# chariot_power_a2.net
KiCad netlist of a schematic drawn in EAGLE
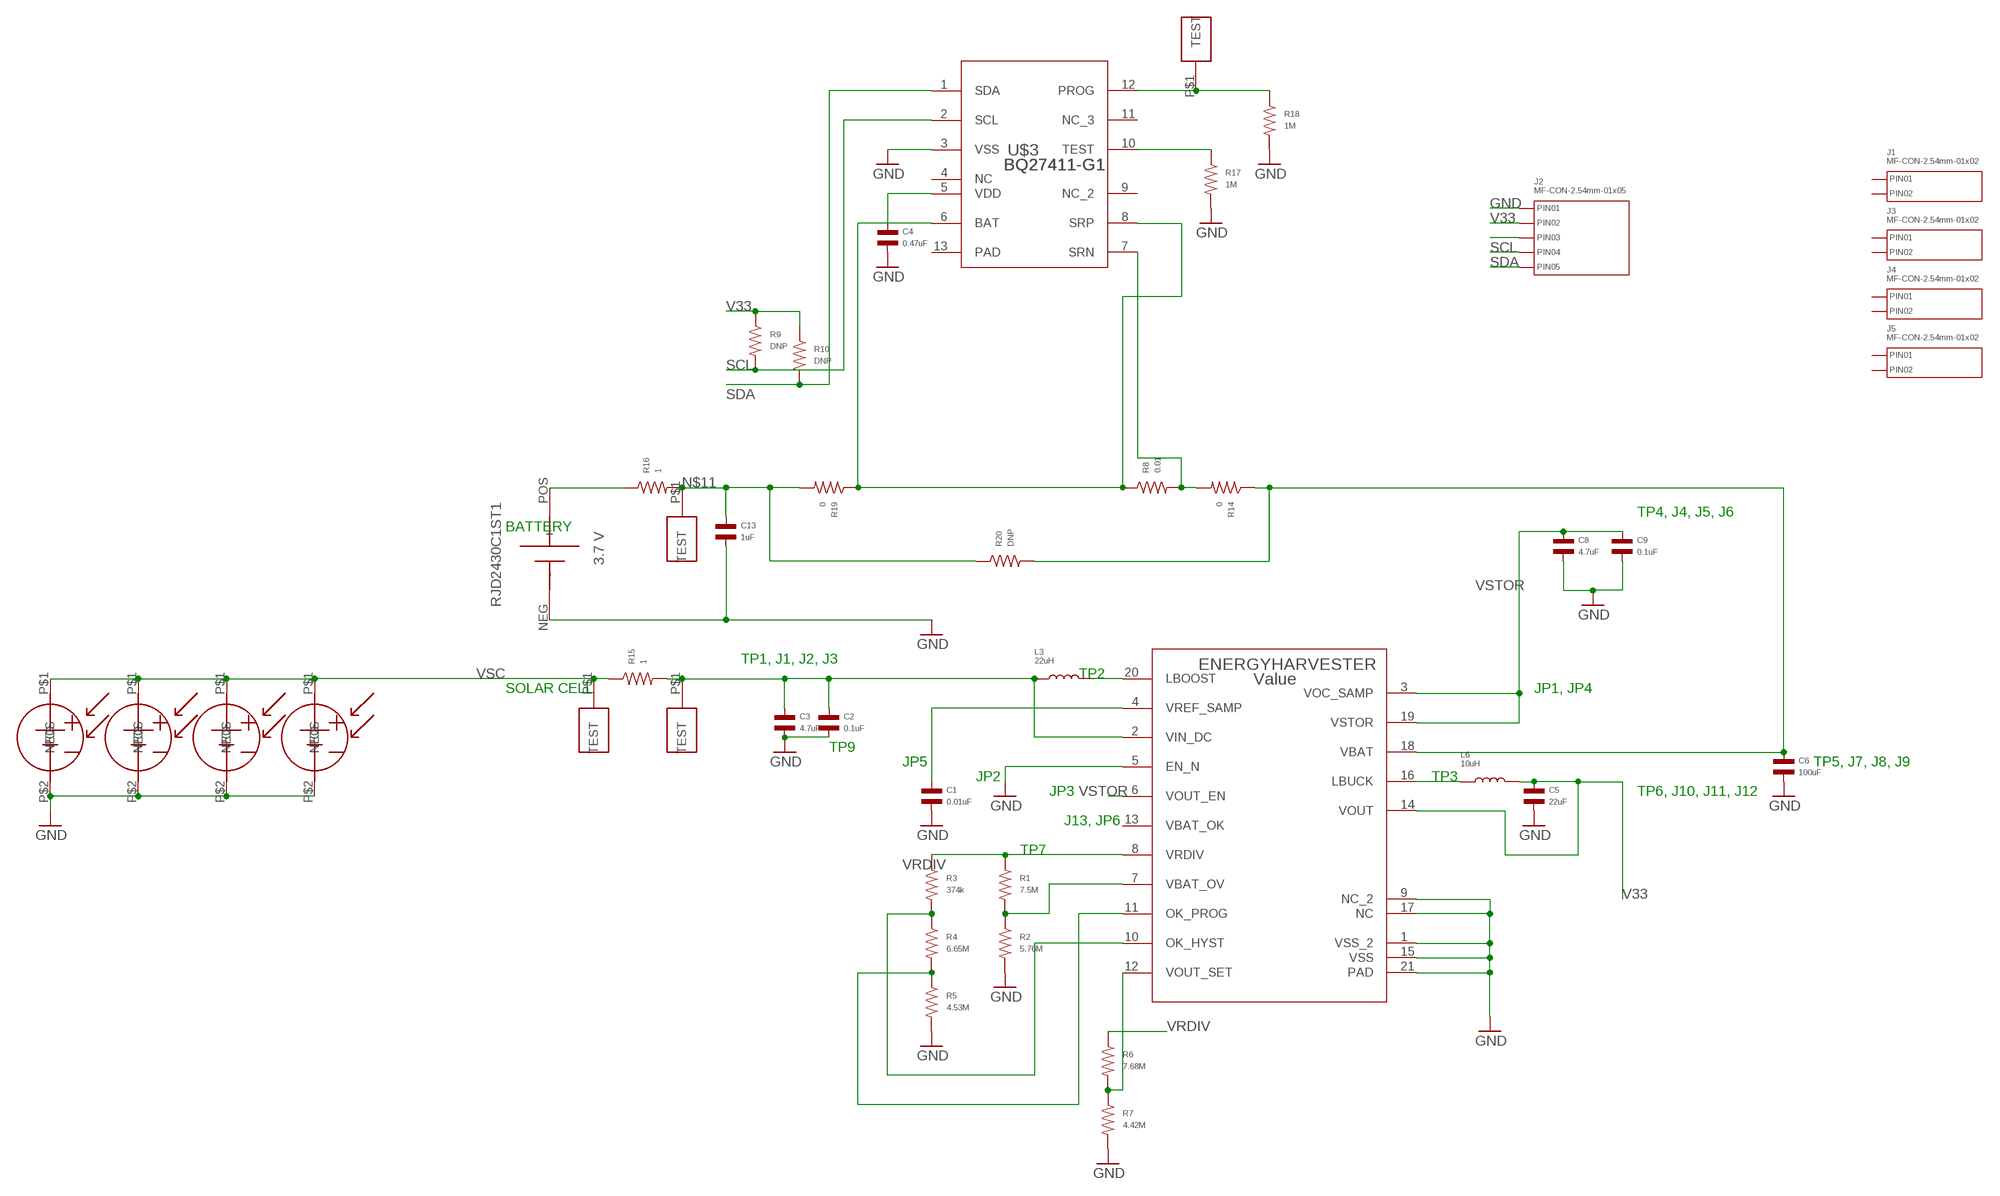
[diagram p0: schematic, sheet 1]

(export (version "E")
  (design (tool "Eeschema 10.0.6"))
  (components
    (comp (ref "C1")
      (value "0.01uF")
      (footprint "eagle-import:C0603")
      (libsource (lib "eagle-import") (part "CAPACITOR_NP_0603"))
    )
    (comp (ref "C2")
      (value "0.1uF")
      (footprint "eagle-import:C0603")
      (libsource (lib "eagle-import") (part "CAPACITOR_NP_0603"))
    )
    (comp (ref "C3")
      (value "4.7uF")
      (footprint "eagle-import:C0603")
      (libsource (lib "eagle-import") (part "CAPACITOR_NP_0603"))
    )
    (comp (ref "C4")
      (value "0.47uF")
      (footprint "eagle-import:C0603")
      (libsource (lib "eagle-import") (part "CAPACITOR_NP_0603"))
    )
    (comp (ref "C5")
      (value "22uF")
      (footprint "eagle-import:C0603")
      (libsource (lib "eagle-import") (part "CAPACITOR_NP_0603"))
    )
    (comp (ref "C6")
      (value "100uF")
      (footprint "eagle-import:C0805")
      (libsource (lib "eagle-import") (part "CAPACITOR_NP_0805"))
    )
    (comp (ref "C8")
      (value "4.7uF")
      (footprint "eagle-import:C0603")
      (libsource (lib "eagle-import") (part "CAPACITOR_NP_0603"))
    )
    (comp (ref "C9")
      (value "0.1uF")
      (footprint "eagle-import:C0603")
      (libsource (lib "eagle-import") (part "CAPACITOR_NP_0603"))
    )
    (comp (ref "C13")
      (value "1uF")
      (footprint "eagle-import:C0603")
      (libsource (lib "eagle-import") (part "CAPACITOR_NP_0603"))
    )
    (comp (ref "ENERGYHARVESTER")
      (value "Value")
      (footprint "eagle-import:RGR0020A")
      (fields
        (field (name "ALTERNATEPARTNUMBER") "BQ25570RGRT")
        (field (name "MANUFACTURER") "Texas Instruments")
        (field (name "PARTNUMBER") "BQ25570RGRR")
      )
      (libsource (lib "eagle-import") (part "BQ25570RGRR"))
    )
    (comp (ref "J1")
      (value "MF-CON-2.54mm-01x02")
      (footprint "eagle-import:PTH_2.54MM_01X02")
      (fields (field (name "HOUSEPART") "YES"))
      (libsource (lib "eagle-import") (part "CON_01X02_PTH_2.54MM"))
    )
    (comp (ref "J2")
      (value "MF-CON-2.54mm-01x05")
      (footprint "eagle-import:PTH_2.54MM_01X05")
      (fields (field (name "HOUSEPART") "YES"))
      (libsource (lib "eagle-import") (part "CON_01X05_PTH_2.54MM"))
    )
    (comp (ref "J3")
      (value "MF-CON-2.54mm-01x02")
      (footprint "eagle-import:PTH_2.54MM_01X02")
      (fields (field (name "HOUSEPART") "YES"))
      (libsource (lib "eagle-import") (part "CON_01X02_PTH_2.54MM"))
    )
    (comp (ref "J4")
      (value "MF-CON-2.54mm-01x02")
      (footprint "eagle-import:PTH_2.54MM_01X02")
      (fields (field (name "HOUSEPART") "YES"))
      (libsource (lib "eagle-import") (part "CON_01X02_PTH_2.54MM"))
    )
    (comp (ref "J5")
      (value "MF-CON-2.54mm-01x02")
      (footprint "eagle-import:PTH_2.54MM_01X02")
      (fields (field (name "HOUSEPART") "YES"))
      (libsource (lib "eagle-import") (part "CON_01X02_PTH_2.54MM"))
    )
    (comp (ref "L3")
      (value "22uH")
      (footprint "eagle-import:L0603")
      (libsource (lib "eagle-import") (part "INDUCTOR_0603"))
    )
    (comp (ref "L6")
      (value "10uH")
      (footprint "eagle-import:L0603")
      (libsource (lib "eagle-import") (part "INDUCTOR_0603"))
    )
    (comp (ref "R1")
      (value "7.5M")
      (footprint "eagle-import:R0603")
      (libsource (lib "eagle-import") (part "RESISTOR_0603"))
    )
    (comp (ref "R2")
      (value "5.76M")
      (footprint "eagle-import:R0603")
      (libsource (lib "eagle-import") (part "RESISTOR_0603"))
    )
    (comp (ref "R3")
      (value "374k")
      (footprint "eagle-import:R0603")
      (libsource (lib "eagle-import") (part "RESISTOR_0603"))
    )
    (comp (ref "R4")
      (value "6.65M")
      (footprint "eagle-import:R0603")
      (libsource (lib "eagle-import") (part "RESISTOR_0603"))
    )
    (comp (ref "R5")
      (value "4.53M")
      (footprint "eagle-import:R0603")
      (libsource (lib "eagle-import") (part "RESISTOR_0603"))
    )
    (comp (ref "R6")
      (value "7.68M")
      (footprint "eagle-import:R0603")
      (libsource (lib "eagle-import") (part "RESISTOR_0603"))
    )
    (comp (ref "R7")
      (value "4.42M")
      (footprint "eagle-import:R0603")
      (libsource (lib "eagle-import") (part "RESISTOR_0603"))
    )
    (comp (ref "R8")
      (value "0.01")
      (footprint "eagle-import:R0603")
      (libsource (lib "eagle-import") (part "RESISTOR_0603"))
    )
    (comp (ref "R9")
      (value "DNP")
      (footprint "eagle-import:R0603")
      (libsource (lib "eagle-import") (part "RESISTOR_0603"))
    )
    (comp (ref "R10")
      (value "DNP")
      (footprint "eagle-import:R0603")
      (libsource (lib "eagle-import") (part "RESISTOR_0603"))
    )
    (comp (ref "R14")
      (value "0")
      (footprint "eagle-import:R0603")
      (libsource (lib "eagle-import") (part "RESISTOR_0603"))
    )
    (comp (ref "R15")
      (value "1")
      (footprint "eagle-import:R0603")
      (libsource (lib "eagle-import") (part "RESISTOR_0603"))
    )
    (comp (ref "R16")
      (value "1")
      (footprint "eagle-import:R0603")
      (libsource (lib "eagle-import") (part "RESISTOR_0603"))
    )
    (comp (ref "R17")
      (value "1M")
      (footprint "eagle-import:R0603")
      (libsource (lib "eagle-import") (part "RESISTOR_0603"))
    )
    (comp (ref "R18")
      (value "1M")
      (footprint "eagle-import:R0603")
      (libsource (lib "eagle-import") (part "RESISTOR_0603"))
    )
    (comp (ref "R19")
      (value "0")
      (footprint "eagle-import:R0603")
      (libsource (lib "eagle-import") (part "RESISTOR_0603"))
    )
    (comp (ref "R20")
      (value "DNP")
      (footprint "eagle-import:R0603")
      (libsource (lib "eagle-import") (part "RESISTOR_0603"))
    )
    (comp (ref "TP4")
      (value "TESTPOINT_LOOP")
      (footprint "eagle-import:TESTPOINT_LOOP")
      (libsource (lib "eagle-import") (part "TESTPOINT_LOOP"))
    )
    (comp (ref "TP6")
      (value "TESTPOINT_LOOP")
      (footprint "eagle-import:TESTPOINT_LOOP")
      (libsource (lib "eagle-import") (part "TESTPOINT_LOOP"))
    )
    (comp (ref "TP7")
      (value "TESTPOINT_LOOP")
      (footprint "eagle-import:TESTPOINT_LOOP")
      (libsource (lib "eagle-import") (part "TESTPOINT_LOOP"))
    )
    (comp (ref "TP8")
      (value "TESTPOINT_LOOP")
      (footprint "eagle-import:TESTPOINT_LOOP")
      (libsource (lib "eagle-import") (part "TESTPOINT_LOOP"))
    )
    (comp (ref "U$2")
      (value "RJD2430C1ST1.")
      (footprint "eagle-import:RJD2430C1ST1")
      (libsource (lib "eagle-import") (part "RJD2430C1ST1."))
    )
    (comp (ref "U$3")
      (value "BQ27411-G1")
      (footprint "eagle-import:DRZ0012A")
      (libsource (lib "eagle-import") (part "BQ27411-G1"))
    )
    (comp (ref "U$4")
      (value "SOLARCELL722")
      (footprint "eagle-import:SOLARCELL722")
      (libsource (lib "eagle-import") (part "SOLARCELL722"))
    )
    (comp (ref "U$5")
      (value "SOLARCELL722")
      (footprint "eagle-import:SOLARCELL722")
      (libsource (lib "eagle-import") (part "SOLARCELL722"))
    )
    (comp (ref "U$6")
      (value "SOLARCELL722")
      (footprint "eagle-import:SOLARCELL722")
      (libsource (lib "eagle-import") (part "SOLARCELL722"))
    )
    (comp (ref "U$7")
      (value "SOLARCELL722")
      (footprint "eagle-import:SOLARCELL722")
      (libsource (lib "eagle-import") (part "SOLARCELL722"))
    )
  )
  (nets
    (net (code "1") (name "/N$11") (class "Default")
      (node (ref "C13") (pin "P$1") (pinfunction "P$1_P$1") (pintype "passive"))
      (node (ref "R16") (pin "P$2") (pinfunction "P$2_P$2") (pintype "passive"))
      (node (ref "R19") (pin "P$2") (pinfunction "P$2_P$2") (pintype "passive"))
      (node (ref "R20") (pin "P$1") (pinfunction "P$1_P$1") (pintype "passive"))
      (node (ref "TP7") (pin "P$1") (pinfunction "TEST_P$1") (pintype "bidirectional"))
    )
    (net (code "2") (name "/SCL") (class "Default")
      (node (ref "J2") (pin "P$4") (pinfunction "PIN4_P$4") (pintype "bidirectional"))
      (node (ref "R9") (pin "P$2") (pinfunction "P$2_P$2") (pintype "passive"))
      (node (ref "U$3") (pin "2") (pinfunction "SCL_2") (pintype "bidirectional"))
    )
    (net (code "3") (name "/SDA") (class "Default")
      (node (ref "J2") (pin "P$5") (pinfunction "PIN5_P$5") (pintype "bidirectional"))
      (node (ref "R10") (pin "P$2") (pinfunction "P$2_P$2") (pintype "passive"))
      (node (ref "U$3") (pin "1") (pinfunction "SDA_1") (pintype "bidirectional"))
    )
    (net (code "4") (name "/V33") (class "Default")
      (node (ref "C5") (pin "P$1") (pinfunction "P$1_P$1") (pintype "passive"))
      (node (ref "ENERGYHARVESTER") (pin "14") (pinfunction "VOUT_14") (pintype "power_in"))
      (node (ref "J2") (pin "P$2") (pinfunction "PIN2_P$2") (pintype "bidirectional"))
      (node (ref "L6") (pin "P$2") (pinfunction "P$2_P$2") (pintype "passive"))
      (node (ref "R10") (pin "P$1") (pinfunction "P$1_P$1") (pintype "passive"))
      (node (ref "R9") (pin "P$1") (pinfunction "P$1_P$1") (pintype "passive"))
    )
    (net (code "5") (name "/VRDIV") (class "Default")
      (node (ref "ENERGYHARVESTER") (pin "8") (pinfunction "VRDIV_8") (pintype "output"))
      (node (ref "R1") (pin "P$1") (pinfunction "P$1_P$1") (pintype "passive"))
      (node (ref "R3") (pin "P$1") (pinfunction "P$1_P$1") (pintype "passive"))
      (node (ref "R6") (pin "P$1") (pinfunction "P$1_P$1") (pintype "passive"))
    )
    (net (code "6") (name "/VSC") (class "Default")
      (node (ref "R15") (pin "P$1") (pinfunction "P$1_P$1") (pintype "passive"))
      (node (ref "TP4") (pin "P$1") (pinfunction "TEST_P$1") (pintype "bidirectional"))
      (node (ref "U$4") (pin "P$1") (pinfunction "POS_P$1") (pintype "bidirectional"))
      (node (ref "U$5") (pin "P$1") (pinfunction "POS_P$1") (pintype "bidirectional"))
      (node (ref "U$6") (pin "P$1") (pinfunction "POS_P$1") (pintype "bidirectional"))
      (node (ref "U$7") (pin "P$1") (pinfunction "POS_P$1") (pintype "bidirectional"))
    )
    (net (code "7") (name "/VSTOR") (class "Default")
      (node (ref "C8") (pin "P$1") (pinfunction "P$1_P$1") (pintype "passive"))
      (node (ref "C9") (pin "P$1") (pinfunction "P$1_P$1") (pintype "passive"))
      (node (ref "ENERGYHARVESTER") (pin "19") (pinfunction "VSTOR_19") (pintype "power_in"))
      (node (ref "ENERGYHARVESTER") (pin "3") (pinfunction "VOC_SAMP_3") (pintype "input"))
      (node (ref "ENERGYHARVESTER") (pin "6") (pinfunction "VOUT_EN_6") (pintype "input"))
    )
    (net (code "8") (name "GND") (class "Default")
      (node (ref "C1") (pin "P$2") (pinfunction "P$2_P$2") (pintype "passive"))
      (node (ref "C13") (pin "P$2") (pinfunction "P$2_P$2") (pintype "passive"))
      (node (ref "C2") (pin "P$2") (pinfunction "P$2_P$2") (pintype "passive"))
      (node (ref "C3") (pin "P$2") (pinfunction "P$2_P$2") (pintype "passive"))
      (node (ref "C4") (pin "P$2") (pinfunction "P$2_P$2") (pintype "passive"))
      (node (ref "C5") (pin "P$2") (pinfunction "P$2_P$2") (pintype "passive"))
      (node (ref "C6") (pin "P$2") (pinfunction "P$2_P$2") (pintype "passive"))
      (node (ref "C8") (pin "P$2") (pinfunction "P$2_P$2") (pintype "passive"))
      (node (ref "C9") (pin "P$2") (pinfunction "P$2_P$2") (pintype "passive"))
      (node (ref "ENERGYHARVESTER") (pin "1") (pinfunction "VSS_2_1") (pintype "power_in"))
      (node (ref "ENERGYHARVESTER") (pin "15") (pinfunction "VSS_15") (pintype "power_in"))
      (node (ref "ENERGYHARVESTER") (pin "17") (pinfunction "NC_17") (pintype "passive"))
      (node (ref "ENERGYHARVESTER") (pin "21") (pinfunction "PAD_21") (pintype "power_in"))
      (node (ref "ENERGYHARVESTER") (pin "5") (pinfunction "EN_N_5") (pintype "input"))
      (node (ref "ENERGYHARVESTER") (pin "9") (pinfunction "NC_2_9") (pintype "power_in"))
      (node (ref "J2") (pin "P$1") (pinfunction "PIN1_P$1") (pintype "bidirectional"))
      (node (ref "R17") (pin "P$2") (pinfunction "P$2_P$2") (pintype "passive"))
      (node (ref "R18") (pin "P$2") (pinfunction "P$2_P$2") (pintype "passive"))
      (node (ref "R2") (pin "P$2") (pinfunction "P$2_P$2") (pintype "passive"))
      (node (ref "R5") (pin "P$2") (pinfunction "P$2_P$2") (pintype "passive"))
      (node (ref "R7") (pin "P$2") (pinfunction "P$2_P$2") (pintype "passive"))
      (node (ref "U$2") (pin "NEG") (pinfunction "-_NEG") (pintype "bidirectional"))
      (node (ref "U$3") (pin "3") (pinfunction "VSS_3") (pintype "power_in"))
      (node (ref "U$4") (pin "P$2") (pinfunction "NEG_P$2") (pintype "bidirectional"))
      (node (ref "U$5") (pin "P$2") (pinfunction "NEG_P$2") (pintype "bidirectional"))
      (node (ref "U$6") (pin "P$2") (pinfunction "NEG_P$2") (pintype "bidirectional"))
      (node (ref "U$7") (pin "P$2") (pinfunction "NEG_P$2") (pintype "bidirectional"))
    )
    (net (code "9") (name "Net-(ENERGYHARVESTER-LBOOST)") (class "Default")
      (node (ref "ENERGYHARVESTER") (pin "20") (pinfunction "LBOOST_20") (pintype "input"))
      (node (ref "L3") (pin "P$2") (pinfunction "P$2_P$2") (pintype "passive"))
    )
    (net (code "10") (name "Net-(ENERGYHARVESTER-LBUCK)") (class "Default")
      (node (ref "ENERGYHARVESTER") (pin "16") (pinfunction "LBUCK_16") (pintype "passive"))
      (node (ref "L6") (pin "P$1") (pinfunction "P$1_P$1") (pintype "passive"))
    )
    (net (code "11") (name "Net-(ENERGYHARVESTER-OK_HYST)") (class "Default")
      (node (ref "ENERGYHARVESTER") (pin "10") (pinfunction "OK_HYST_10") (pintype "input"))
      (node (ref "R3") (pin "P$2") (pinfunction "P$2_P$2") (pintype "passive"))
      (node (ref "R4") (pin "P$1") (pinfunction "P$1_P$1") (pintype "passive"))
    )
    (net (code "12") (name "Net-(ENERGYHARVESTER-OK_PROG)") (class "Default")
      (node (ref "ENERGYHARVESTER") (pin "11") (pinfunction "OK_PROG_11") (pintype "input"))
      (node (ref "R4") (pin "P$2") (pinfunction "P$2_P$2") (pintype "passive"))
      (node (ref "R5") (pin "P$1") (pinfunction "P$1_P$1") (pintype "passive"))
    )
    (net (code "13") (name "Net-(ENERGYHARVESTER-VBAT)") (class "Default")
      (node (ref "C6") (pin "P$1") (pinfunction "P$1_P$1") (pintype "passive"))
      (node (ref "ENERGYHARVESTER") (pin "18") (pinfunction "VBAT_18") (pintype "bidirectional"))
      (node (ref "R14") (pin "P$1") (pinfunction "P$1_P$1") (pintype "passive"))
      (node (ref "R20") (pin "P$2") (pinfunction "P$2_P$2") (pintype "passive"))
    )
    (net (code "14") (name "Net-(ENERGYHARVESTER-VBAT_OV)") (class "Default")
      (node (ref "ENERGYHARVESTER") (pin "7") (pinfunction "VBAT_OV_7") (pintype "input"))
      (node (ref "R1") (pin "P$2") (pinfunction "P$2_P$2") (pintype "passive"))
      (node (ref "R2") (pin "P$1") (pinfunction "P$1_P$1") (pintype "passive"))
    )
    (net (code "15") (name "Net-(ENERGYHARVESTER-VIN_DC)") (class "Default")
      (node (ref "C2") (pin "P$1") (pinfunction "P$1_P$1") (pintype "passive"))
      (node (ref "C3") (pin "P$1") (pinfunction "P$1_P$1") (pintype "passive"))
      (node (ref "ENERGYHARVESTER") (pin "2") (pinfunction "VIN_DC_2") (pintype "power_in"))
      (node (ref "L3") (pin "P$1") (pinfunction "P$1_P$1") (pintype "passive"))
      (node (ref "R15") (pin "P$2") (pinfunction "P$2_P$2") (pintype "passive"))
      (node (ref "TP6") (pin "P$1") (pinfunction "TEST_P$1") (pintype "bidirectional"))
    )
    (net (code "16") (name "Net-(ENERGYHARVESTER-VOUT_SET)") (class "Default")
      (node (ref "ENERGYHARVESTER") (pin "12") (pinfunction "VOUT_SET_12") (pintype "input"))
      (node (ref "R6") (pin "P$2") (pinfunction "P$2_P$2") (pintype "passive"))
      (node (ref "R7") (pin "P$1") (pinfunction "P$1_P$1") (pintype "passive"))
    )
    (net (code "17") (name "Net-(ENERGYHARVESTER-VREF_SAMP)") (class "Default")
      (node (ref "C1") (pin "P$1") (pinfunction "P$1_P$1") (pintype "passive"))
      (node (ref "ENERGYHARVESTER") (pin "4") (pinfunction "VREF_SAMP_4") (pintype "input"))
    )
    (net (code "18") (name "Net-(TP8-TEST)") (class "Default")
      (node (ref "R18") (pin "P$1") (pinfunction "P$1_P$1") (pintype "passive"))
      (node (ref "TP8") (pin "P$1") (pinfunction "TEST_P$1") (pintype "bidirectional"))
      (node (ref "U$3") (pin "12") (pinfunction "PROG_12") (pintype "output"))
    )
    (net (code "19") (name "Net-(U$2-+)") (class "Default")
      (node (ref "R16") (pin "P$1") (pinfunction "P$1_P$1") (pintype "passive"))
      (node (ref "U$2") (pin "POS") (pinfunction "+_POS") (pintype "bidirectional"))
    )
    (net (code "20") (name "Net-(U$3-BAT)") (class "Default")
      (node (ref "R19") (pin "P$1") (pinfunction "P$1_P$1") (pintype "passive"))
      (node (ref "R8") (pin "P$1") (pinfunction "P$1_P$1") (pintype "passive"))
      (node (ref "U$3") (pin "6") (pinfunction "BAT_6") (pintype "power_in"))
      (node (ref "U$3") (pin "8") (pinfunction "SRP_8") (pintype "bidirectional"))
    )
    (net (code "21") (name "Net-(U$3-SRN)") (class "Default")
      (node (ref "R14") (pin "P$2") (pinfunction "P$2_P$2") (pintype "passive"))
      (node (ref "R8") (pin "P$2") (pinfunction "P$2_P$2") (pintype "passive"))
      (node (ref "U$3") (pin "7") (pinfunction "SRN_7") (pintype "bidirectional"))
    )
    (net (code "22") (name "Net-(U$3-TEST)") (class "Default")
      (node (ref "R17") (pin "P$1") (pinfunction "P$1_P$1") (pintype "passive"))
      (node (ref "U$3") (pin "10") (pinfunction "TEST_10") (pintype "input"))
    )
    (net (code "23") (name "Net-(U$3-VDD)") (class "Default")
      (node (ref "C4") (pin "P$1") (pinfunction "P$1_P$1") (pintype "passive"))
      (node (ref "U$3") (pin "5") (pinfunction "VDD_5") (pintype "power_in"))
    )
    (net (code "24") (name "unconnected-(ENERGYHARVESTER-VBAT_OK-Pad13)") (class "Default")
      (node (ref "ENERGYHARVESTER") (pin "13") (pinfunction "VBAT_OK_13") (pintype "output"))
    )
    (net (code "25") (name "unconnected-(J1-PIN1-PadP$1)") (class "Default")
      (node (ref "J1") (pin "P$1") (pinfunction "PIN1_P$1") (pintype "bidirectional"))
    )
    (net (code "26") (name "unconnected-(J1-PIN2-PadP$2)") (class "Default")
      (node (ref "J1") (pin "P$2") (pinfunction "PIN2_P$2") (pintype "bidirectional"))
    )
    (net (code "27") (name "unconnected-(J2-PIN3-PadP$3)") (class "Default")
      (node (ref "J2") (pin "P$3") (pinfunction "PIN3_P$3") (pintype "bidirectional"))
    )
    (net (code "28") (name "unconnected-(J3-PIN1-PadP$1)") (class "Default")
      (node (ref "J3") (pin "P$1") (pinfunction "PIN1_P$1") (pintype "bidirectional"))
    )
    (net (code "29") (name "unconnected-(J3-PIN2-PadP$2)") (class "Default")
      (node (ref "J3") (pin "P$2") (pinfunction "PIN2_P$2") (pintype "bidirectional"))
    )
    (net (code "30") (name "unconnected-(J4-PIN1-PadP$1)") (class "Default")
      (node (ref "J4") (pin "P$1") (pinfunction "PIN1_P$1") (pintype "bidirectional"))
    )
    (net (code "31") (name "unconnected-(J4-PIN2-PadP$2)") (class "Default")
      (node (ref "J4") (pin "P$2") (pinfunction "PIN2_P$2") (pintype "bidirectional"))
    )
    (net (code "32") (name "unconnected-(J5-PIN1-PadP$1)") (class "Default")
      (node (ref "J5") (pin "P$1") (pinfunction "PIN1_P$1") (pintype "bidirectional"))
    )
    (net (code "33") (name "unconnected-(J5-PIN2-PadP$2)") (class "Default")
      (node (ref "J5") (pin "P$2") (pinfunction "PIN2_P$2") (pintype "bidirectional"))
    )
    (net (code "34") (name "unconnected-(U$3-NC-Pad4)") (class "Default")
      (node (ref "U$3") (pin "4") (pinfunction "NC_4") (pintype "passive"))
    )
    (net (code "35") (name "unconnected-(U$3-NC_2-Pad9)") (class "Default")
      (node (ref "U$3") (pin "9") (pinfunction "NC_2_9") (pintype "passive"))
    )
    (net (code "36") (name "unconnected-(U$3-NC_3-Pad11)") (class "Default")
      (node (ref "U$3") (pin "11") (pinfunction "NC_3_11") (pintype "passive"))
    )
    (net (code "37") (name "unconnected-(U$3-PAD-Pad13)") (class "Default")
      (node (ref "U$3") (pin "13") (pinfunction "PAD_13") (pintype "passive"))
    )
  )
)
